# hierarchy.net
KiCad netlist of a schematic drawn in Altium Designer
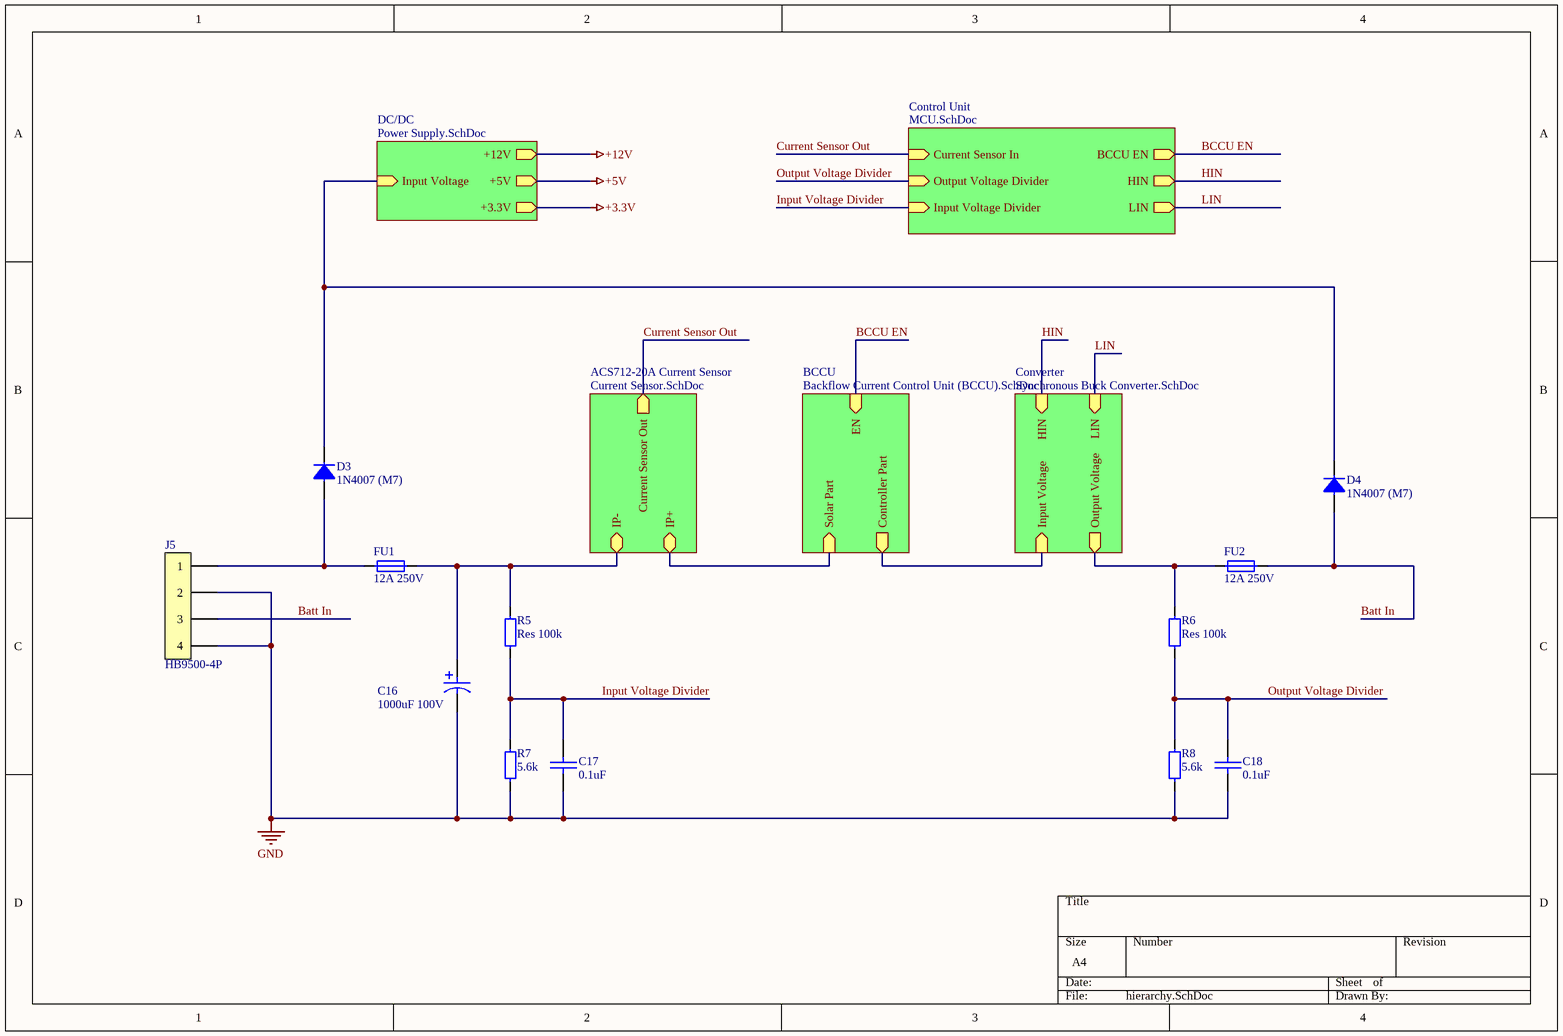
[diagram p0: hierarchy.SchDoc]

(export (version "E")
  (design (tool "Eeschema 10.0.6"))
  (components
    (comp (ref "C16")
      (value "1000uF 100V")
      (description "1000мкФ, 100В, 105°C, 20%, 18*40мм P:7,5мм")
      (libsource (lib "Altium_Library") (part "Capacitor 1000uF 100V"))
    )
    (comp (ref "C17")
      (value "0.1uF")
      (footprint "0805 Capicator")
      (description "0.1uF X7R 25V 10% 0805")
      (fields
        (field (name "MANUFACTURER") "Murata Manufacturing")
        (field (name "PART NUMBER") "GRM21BR71E104KA01L")
      )
      (libsource (lib "BRT_Components") (part "Cap 0.1uF (0805)"))
    )
    (comp (ref "C18")
      (value "0.1uF")
      (footprint "0805 Capicator")
      (description "0.1uF X7R 25V 10% 0805")
      (fields
        (field (name "MANUFACTURER") "Murata Manufacturing")
        (field (name "PART NUMBER") "GRM21BR71E104KA01L")
      )
      (libsource (lib "BRT_Components") (part "Cap 0.1uF (0805)"))
    )
    (comp (ref "D3")
      (value "1N4007 (M7)")
      (footprint "SMA")
      (description "Diode 1A 1000V")
      (libsource (lib "Altium_Library") (part "Diode 1N4007 (M7)"))
    )
    (comp (ref "D4")
      (value "1N4007 (M7)")
      (footprint "SMA")
      (description "Diode 1A 1000V")
      (libsource (lib "Altium_Library") (part "Diode 1N4007 (M7)"))
    )
    (comp (ref "FU1")
      (value "12A 250V")
      (footprint "Fuse Glass 5x20")
      (description "Fusible link H520B 12A 250 V, 5×20, Fast acting fuse (blister)")
      (libsource (lib "Altium_Library") (part "Fuse 12A 250V"))
    )
    (comp (ref "FU2")
      (value "12A 250V")
      (footprint "Fuse Glass 5x20")
      (description "Fusible link H520B 12A 250 V, 5×20, Fast acting fuse (blister)")
      (libsource (lib "Altium_Library") (part "Fuse 12A 250V"))
    )
    (comp (ref "J5")
      (value "HB9500-4P")
      (footprint "HB-9500-9.5-4p")
      (description "Barrier P-9.5mm terminal")
      (libsource (lib "Altium_Library") (part "Barrier Terminal Connector HB9500-4P"))
    )
    (comp (ref "R5")
      (value "Res 100k")
      (footprint "0805 Resistor")
      (description "0.125W 0805 100k, 1%")
      (fields (field (name "PART NUMBER") "RC0805FR-07100KL") (field (name "MANUFACTURER") "Taiwan"))
      (libsource (lib "BRT_Components") (part "Res 100k (0805)"))
    )
    (comp (ref "R6")
      (value "Res 100k")
      (footprint "0805 Resistor")
      (description "0.125W 0805 100k, 1%")
      (fields (field (name "PART NUMBER") "RC0805FR-07100KL") (field (name "MANUFACTURER") "Taiwan"))
      (libsource (lib "BRT_Components") (part "Res 100k (0805)"))
    )
    (comp (ref "R7")
      (value "5.6k")
      (footprint "0805 Resistor")
      (description "0805 0.125W 5% 5,6 kOhm")
      (libsource (lib "Altium_Library") (part "Resisot 5.6k (0805)"))
    )
    (comp (ref "R8")
      (value "5.6k")
      (footprint "0805 Resistor")
      (description "0805 0.125W 5% 5,6 kOhm")
      (libsource (lib "Altium_Library") (part "Resisot 5.6k (0805)"))
    )
  )
  (nets
    (net (code "5") (name "/Batt In") (class "Default")
      (node (ref "D4") (pin "1") (pinfunction "1_1") (pintype "passive"))
      (node (ref "FU2") (pin "2") (pinfunction "2_2") (pintype "passive"))
      (node (ref "J5") (pin "3") (pinfunction "3_3") (pintype "passive"))
    )
    (net (code "10") (name "/IP-") (class "Default")
      (node (ref "C16") (pin "2") (pinfunction "2_2") (pintype "passive"))
      (node (ref "FU1") (pin "2") (pinfunction "2_2") (pintype "passive"))
      (node (ref "R5") (pin "2") (pinfunction "2_2") (pintype "passive"))
    )
    (net (code "11") (name "/Input Voltage") (class "Default")
      (node (ref "D3") (pin "2") (pinfunction "2_2") (pintype "passive"))
      (node (ref "D4") (pin "2") (pinfunction "2_2") (pintype "passive"))
    )
    (net (code "12") (name "/Input Voltage Divider") (class "Default")
      (node (ref "C17") (pin "2") (pinfunction "2_2") (pintype "passive"))
      (node (ref "R5") (pin "1") (pinfunction "1_1") (pintype "passive"))
      (node (ref "R7") (pin "2") (pinfunction "2_2") (pintype "passive"))
    )
    (net (code "14") (name "/Output Voltage") (class "Default")
      (node (ref "FU2") (pin "1") (pinfunction "1_1") (pintype "passive"))
      (node (ref "R6") (pin "2") (pinfunction "2_2") (pintype "passive"))
    )
    (net (code "15") (name "/Output Voltage Divider") (class "Default")
      (node (ref "C18") (pin "2") (pinfunction "2_2") (pintype "passive"))
      (node (ref "R6") (pin "1") (pinfunction "1_1") (pintype "passive"))
      (node (ref "R8") (pin "2") (pinfunction "2_2") (pintype "passive"))
    )
    (net (code "16") (name "GND") (class "Default")
      (node (ref "C16") (pin "1") (pinfunction "1_1") (pintype "passive"))
      (node (ref "C17") (pin "1") (pinfunction "1_1") (pintype "passive"))
      (node (ref "C18") (pin "1") (pinfunction "1_1") (pintype "passive"))
      (node (ref "J5") (pin "2") (pinfunction "2_2") (pintype "passive"))
      (node (ref "J5") (pin "4") (pinfunction "4_4") (pintype "passive"))
      (node (ref "R7") (pin "1") (pinfunction "1_1") (pintype "passive"))
      (node (ref "R8") (pin "1") (pinfunction "1_1") (pintype "passive"))
    )
    (net (code "17") (name "Net-(D3-Pad1)") (class "Default")
      (node (ref "D3") (pin "1") (pinfunction "1_1") (pintype "passive"))
      (node (ref "FU1") (pin "1") (pinfunction "1_1") (pintype "passive"))
      (node (ref "J5") (pin "1") (pinfunction "1_1") (pintype "passive"))
    )
  )
)
